# nano.net
KiCad netlist of a schematic drawn in EAGLE
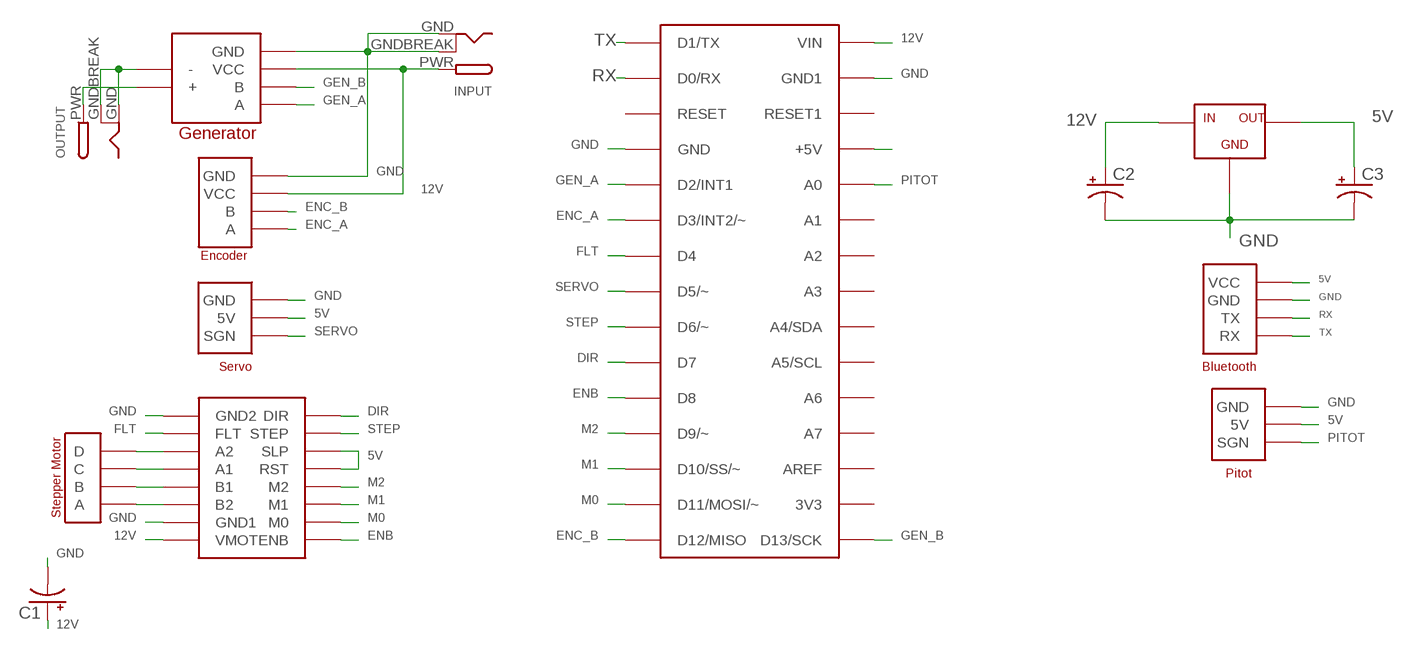
[diagram p0: schematic, sheet 1]

(export (version "E")
  (design (tool "Eeschema 10.0.6"))
  (components
    (comp (ref "C1")
      (value "100UF-25V-20%(PTH)")
      (footprint "eagle-import:CPOL-RADIAL-100UF-25V")
      (libsource (lib "eagle-import") (part "100UF-25V-20%(PTH)"))
    )
    (comp (ref "C2")
      (value "100UF-25V-20%(PTH)")
      (footprint "eagle-import:CPOL-RADIAL-100UF-25V")
      (libsource (lib "eagle-import") (part "100UF-25V-20%(PTH)"))
    )
    (comp (ref "C3")
      (value "100UF-25V-20%(PTH)")
      (footprint "eagle-import:CPOL-RADIAL-100UF-25V")
      (libsource (lib "eagle-import") (part "100UF-25V-20%(PTH)"))
    )
    (comp (ref "INPUT")
      (value "DCBARRELPTH")
      (footprint "eagle-import:DCJACK_2MM_PTH")
      (libsource (lib "eagle-import") (part "DCBARRELPTH"))
    )
    (comp (ref "NANO")
      (value "ARDUINONANO")
      (footprint "eagle-import:PDIP-32")
      (libsource (lib "eagle-import") (part "ARDUINONANO"))
    )
    (comp (ref "OUTPUT")
      (value "DCBARRELPTH")
      (footprint "eagle-import:DCJACK_2MM_PTH")
      (libsource (lib "eagle-import") (part "DCBARRELPTH"))
    )
    (comp (ref "U$1")
      (value "HC06")
      (footprint "eagle-import:HC06")
      (libsource (lib "eagle-import") (part "HC06"))
    )
    (comp (ref "U$2")
      (value "ENCODER")
      (footprint "eagle-import:ENCODER")
      (libsource (lib "eagle-import") (part "ENCODER"))
    )
    (comp (ref "U$3")
      (value "PITOT")
      (footprint "eagle-import:PITOT")
      (libsource (lib "eagle-import") (part "PITOT"))
    )
    (comp (ref "U$4")
      (value "STEPPER")
      (footprint "eagle-import:STEPPER")
      (libsource (lib "eagle-import") (part "STEPPER"))
    )
    (comp (ref "U$5")
      (value "STEPPER_DRIVER")
      (footprint "eagle-import:STEPPER_DRIVER")
      (libsource (lib "eagle-import") (part "STEPPER_DRIVER"))
    )
    (comp (ref "U$6")
      (value "SERVO")
      (footprint "eagle-import:SERVO")
      (libsource (lib "eagle-import") (part "SERVO"))
    )
    (comp (ref "U$7")
      (value "GENERATOR")
      (footprint "eagle-import:GENERATOR")
      (libsource (lib "eagle-import") (part "GENERATOR"))
    )
    (comp (ref "U$8")
      (value "7805")
      (footprint "eagle-import:7805")
      (libsource (lib "eagle-import") (part "7805"))
    )
  )
  (nets
    (net (code "1") (name "/5V") (class "Default")
      (node (ref "C3") (pin "1") (pinfunction "+_1") (pintype "passive"))
      (node (ref "NANO") (pin "+5V") (pinfunction "+5V_+5V") (pintype "bidirectional"))
      (node (ref "U$1") (pin "VCC") (pinfunction "VCC_VCC") (pintype "bidirectional"))
      (node (ref "U$3") (pin "5V") (pinfunction "5V_5V") (pintype "bidirectional"))
      (node (ref "U$5") (pin "RST") (pinfunction "RST_RST") (pintype "bidirectional"))
      (node (ref "U$5") (pin "SLP") (pinfunction "SLP_SLP") (pintype "bidirectional"))
      (node (ref "U$6") (pin "5V") (pinfunction "5V_5V") (pintype "bidirectional"))
      (node (ref "U$8") (pin "OUT") (pinfunction "OUT_OUT") (pintype "bidirectional"))
    )
    (net (code "2") (name "/12V") (class "Default")
      (node (ref "C1") (pin "1") (pinfunction "+_1") (pintype "passive"))
      (node (ref "C2") (pin "1") (pinfunction "+_1") (pintype "passive"))
      (node (ref "INPUT") (pin "PWR") (pinfunction "PWR_PWR") (pintype "power_in"))
      (node (ref "NANO") (pin "VIN") (pinfunction "VIN_VIN") (pintype "bidirectional"))
      (node (ref "U$2") (pin "VCC") (pinfunction "VCC_VCC") (pintype "bidirectional"))
      (node (ref "U$5") (pin "VMOT") (pinfunction "VMOT_VMOT") (pintype "bidirectional"))
      (node (ref "U$7") (pin "VCC") (pinfunction "VCC_VCC") (pintype "bidirectional"))
      (node (ref "U$8") (pin "IN") (pinfunction "IN_IN") (pintype "bidirectional"))
    )
    (net (code "3") (name "/DIR") (class "Default")
      (node (ref "NANO") (pin "D7") (pinfunction "D7_D7") (pintype "bidirectional"))
      (node (ref "U$5") (pin "DIR") (pinfunction "DIR_DIR") (pintype "bidirectional"))
    )
    (net (code "4") (name "/ENB") (class "Default")
      (node (ref "NANO") (pin "D8") (pinfunction "D8_D8") (pintype "bidirectional"))
      (node (ref "U$5") (pin "ENB") (pinfunction "ENB_ENB") (pintype "bidirectional"))
    )
    (net (code "5") (name "/ENC_A") (class "Default")
      (node (ref "NANO") (pin "D3") (pinfunction "D3/INT2/~{}_D3") (pintype "bidirectional"))
      (node (ref "U$2") (pin "A") (pinfunction "A_A") (pintype "bidirectional"))
    )
    (net (code "6") (name "/ENC_B") (class "Default")
      (node (ref "NANO") (pin "D12") (pinfunction "D12/MISO_D12") (pintype "bidirectional"))
      (node (ref "U$2") (pin "B") (pinfunction "B_B") (pintype "bidirectional"))
    )
    (net (code "7") (name "/FLT") (class "Default")
      (node (ref "NANO") (pin "D4") (pinfunction "D4_D4") (pintype "bidirectional"))
      (node (ref "U$5") (pin "FLT") (pinfunction "FLT_FLT") (pintype "bidirectional"))
    )
    (net (code "8") (name "/GEN_A") (class "Default")
      (node (ref "NANO") (pin "D2") (pinfunction "D2/INT1_D2") (pintype "bidirectional"))
      (node (ref "U$7") (pin "A") (pinfunction "A_A") (pintype "bidirectional"))
    )
    (net (code "9") (name "/GEN_B") (class "Default")
      (node (ref "NANO") (pin "D13") (pinfunction "D13/SCK_D13") (pintype "bidirectional"))
      (node (ref "U$7") (pin "B") (pinfunction "B_B") (pintype "bidirectional"))
    )
    (net (code "10") (name "/GND") (class "Default")
      (node (ref "C1") (pin "2") (pinfunction "-_2") (pintype "passive"))
      (node (ref "C2") (pin "2") (pinfunction "-_2") (pintype "passive"))
      (node (ref "C3") (pin "2") (pinfunction "-_2") (pintype "passive"))
      (node (ref "INPUT") (pin "GND") (pinfunction "GND_GND") (pintype "power_in"))
      (node (ref "INPUT") (pin "GNDBREAK") (pinfunction "GNDBREAK_GNDBREAK") (pintype "power_in"))
      (node (ref "NANO") (pin "GND") (pinfunction "GND_GND") (pintype "bidirectional"))
      (node (ref "NANO") (pin "GND1") (pinfunction "GND1_GND1") (pintype "bidirectional"))
      (node (ref "OUTPUT") (pin "GND") (pinfunction "GND_GND") (pintype "power_in"))
      (node (ref "OUTPUT") (pin "GNDBREAK") (pinfunction "GNDBREAK_GNDBREAK") (pintype "power_in"))
      (node (ref "U$1") (pin "GND") (pinfunction "GND_GND") (pintype "bidirectional"))
      (node (ref "U$2") (pin "GND") (pinfunction "GND_GND") (pintype "bidirectional"))
      (node (ref "U$3") (pin "GND") (pinfunction "GND_GND") (pintype "bidirectional"))
      (node (ref "U$5") (pin "GND") (pinfunction "GND1_GND") (pintype "bidirectional"))
      (node (ref "U$5") (pin "GND1") (pinfunction "GND2_GND1") (pintype "bidirectional"))
      (node (ref "U$6") (pin "GND") (pinfunction "GND_GND") (pintype "bidirectional"))
      (node (ref "U$7") (pin "-") (pinfunction "-_-") (pintype "bidirectional"))
      (node (ref "U$7") (pin "GND") (pinfunction "GND_GND") (pintype "bidirectional"))
      (node (ref "U$8") (pin "GND") (pinfunction "GND_GND") (pintype "bidirectional"))
    )
    (net (code "11") (name "/M0") (class "Default")
      (node (ref "NANO") (pin "D11") (pinfunction "D11/MOSI/~{}_D11") (pintype "bidirectional"))
      (node (ref "U$5") (pin "M0") (pinfunction "M0_M0") (pintype "bidirectional"))
    )
    (net (code "12") (name "/M1") (class "Default")
      (node (ref "NANO") (pin "D10") (pinfunction "D10/SS/~{}_D10") (pintype "bidirectional"))
      (node (ref "U$5") (pin "M1") (pinfunction "M1_M1") (pintype "bidirectional"))
    )
    (net (code "13") (name "/M2") (class "Default")
      (node (ref "NANO") (pin "D9") (pinfunction "D9/~{}_D9") (pintype "bidirectional"))
      (node (ref "U$5") (pin "M2") (pinfunction "M2_M2") (pintype "bidirectional"))
    )
    (net (code "14") (name "/PITOT") (class "Default")
      (node (ref "NANO") (pin "A0") (pinfunction "A0_A0") (pintype "bidirectional"))
      (node (ref "U$3") (pin "SGN") (pinfunction "SGN_SGN") (pintype "bidirectional"))
    )
    (net (code "15") (name "/RX") (class "Default")
      (node (ref "NANO") (pin "D0/RX") (pinfunction "D0/RX_D0/RX") (pintype "bidirectional"))
      (node (ref "U$1") (pin "TX") (pinfunction "TX_TX") (pintype "bidirectional"))
    )
    (net (code "16") (name "/SERVO") (class "Default")
      (node (ref "NANO") (pin "D5") (pinfunction "D5/~{}_D5") (pintype "bidirectional"))
      (node (ref "U$6") (pin "SGN") (pinfunction "SGN_SGN") (pintype "bidirectional"))
    )
    (net (code "17") (name "/STEP") (class "Default")
      (node (ref "NANO") (pin "D6") (pinfunction "D6/~{}_D6") (pintype "bidirectional"))
      (node (ref "U$5") (pin "STEP") (pinfunction "STEP_STEP") (pintype "bidirectional"))
    )
    (net (code "18") (name "/TX") (class "Default")
      (node (ref "NANO") (pin "D1/TX") (pinfunction "D1/TX_D1/TX") (pintype "bidirectional"))
      (node (ref "U$1") (pin "RX") (pinfunction "RX_RX") (pintype "bidirectional"))
    )
    (net (code "19") (name "Net-(OUTPUT-PadPWR)") (class "Default")
      (node (ref "OUTPUT") (pin "PWR") (pinfunction "PWR_PWR") (pintype "power_in"))
      (node (ref "U$7") (pin "+") (pinfunction "+_+") (pintype "bidirectional"))
    )
    (net (code "20") (name "Net-(U$4-PadA)") (class "Default")
      (node (ref "U$4") (pin "A") (pinfunction "A_A") (pintype "bidirectional"))
      (node (ref "U$5") (pin "B2") (pinfunction "B2_B2") (pintype "bidirectional"))
    )
    (net (code "21") (name "Net-(U$4-PadB)") (class "Default")
      (node (ref "U$4") (pin "B") (pinfunction "B_B") (pintype "bidirectional"))
      (node (ref "U$5") (pin "B1") (pinfunction "B1_B1") (pintype "bidirectional"))
    )
    (net (code "22") (name "Net-(U$4-PadC)") (class "Default")
      (node (ref "U$4") (pin "C") (pinfunction "C_C") (pintype "bidirectional"))
      (node (ref "U$5") (pin "A1") (pinfunction "A1_A1") (pintype "bidirectional"))
    )
    (net (code "23") (name "Net-(U$4-PadD)") (class "Default")
      (node (ref "U$4") (pin "D") (pinfunction "D_D") (pintype "bidirectional"))
      (node (ref "U$5") (pin "A2") (pinfunction "A2_A2") (pintype "bidirectional"))
    )
    (net (code "24") (name "unconnected-(NANO-A4{slash}SDA-PadA4)") (class "Default")
      (node (ref "NANO") (pin "A4") (pinfunction "A4/SDA_A4") (pintype "bidirectional"))
    )
    (net (code "25") (name "unconnected-(NANO-A5{slash}SCL-PadA5)") (class "Default")
      (node (ref "NANO") (pin "A5") (pinfunction "A5/SCL_A5") (pintype "bidirectional"))
    )
    (net (code "26") (name "unconnected-(NANO-Pad3V3)") (class "Default")
      (node (ref "NANO") (pin "3V3") (pinfunction "3V3_3V3") (pintype "bidirectional"))
    )
    (net (code "27") (name "unconnected-(NANO-PadA1)") (class "Default")
      (node (ref "NANO") (pin "A1") (pinfunction "A1_A1") (pintype "bidirectional"))
    )
    (net (code "28") (name "unconnected-(NANO-PadA2)") (class "Default")
      (node (ref "NANO") (pin "A2") (pinfunction "A2_A2") (pintype "bidirectional"))
    )
    (net (code "29") (name "unconnected-(NANO-PadA3)") (class "Default")
      (node (ref "NANO") (pin "A3") (pinfunction "A3_A3") (pintype "bidirectional"))
    )
    (net (code "30") (name "unconnected-(NANO-PadA6)") (class "Default")
      (node (ref "NANO") (pin "A6") (pinfunction "A6_A6") (pintype "bidirectional"))
    )
    (net (code "31") (name "unconnected-(NANO-PadA7)") (class "Default")
      (node (ref "NANO") (pin "A7") (pinfunction "A7_A7") (pintype "bidirectional"))
    )
    (net (code "32") (name "unconnected-(NANO-PadAREF)") (class "Default")
      (node (ref "NANO") (pin "AREF") (pinfunction "AREF_AREF") (pintype "bidirectional"))
    )
    (net (code "33") (name "unconnected-(NANO-PadRESET)") (class "Default")
      (node (ref "NANO") (pin "RESET") (pinfunction "RESET_RESET") (pintype "bidirectional"))
    )
    (net (code "34") (name "unconnected-(NANO-PadRESET1)") (class "Default")
      (node (ref "NANO") (pin "RESET1") (pinfunction "RESET1_RESET1") (pintype "bidirectional"))
    )
  )
)
